# tie-flash-cfg.net
KiCad netlist of a schematic drawn in Altium Designer
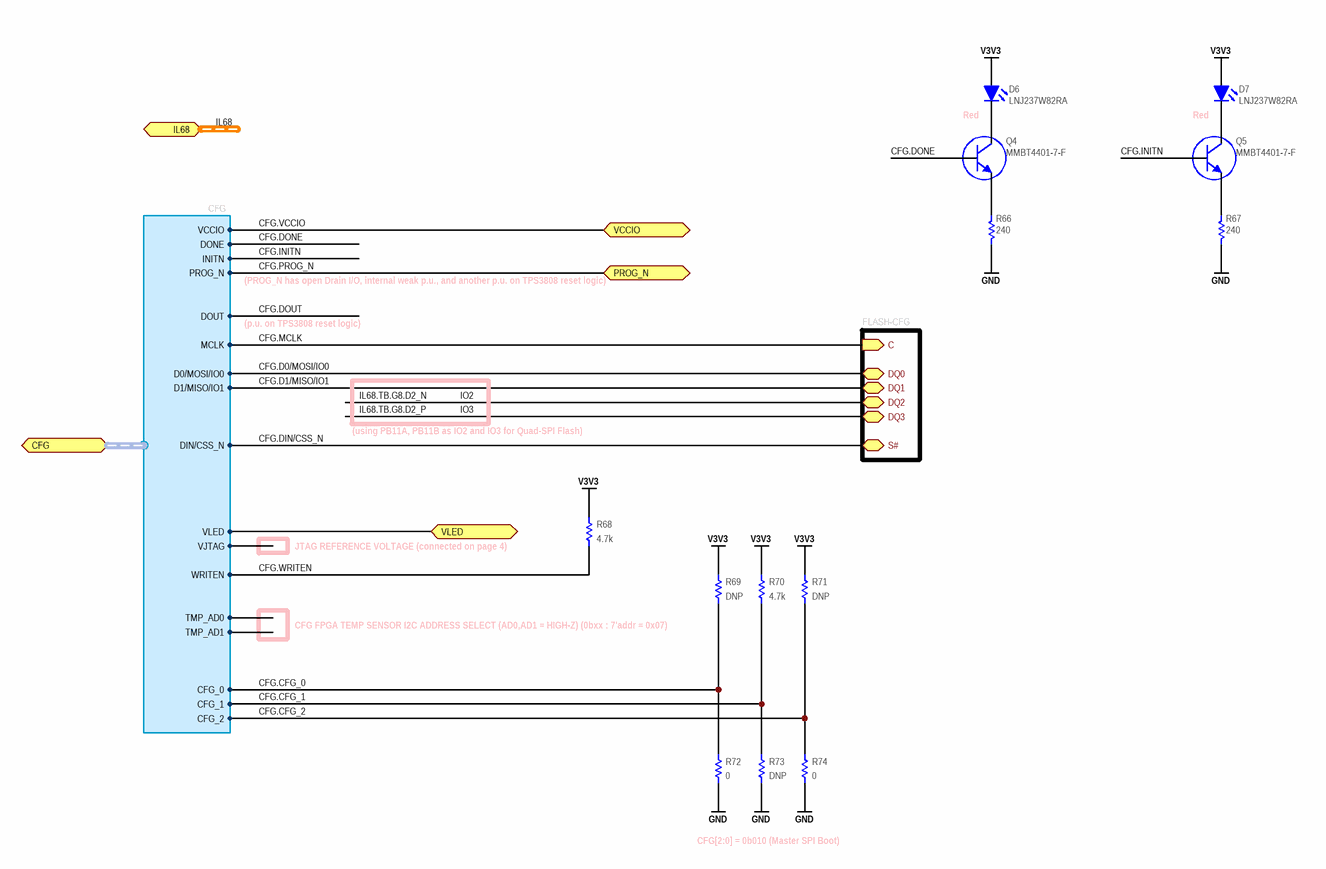
[diagram p0: tie-flash-cfg.SchDoc]

(export (version "E")
  (design (tool "Eeschema 10.0.6"))
  (components
    (comp (ref "D6")
      (value "LNJ237W82RA")
      (footprint "0603_LED")
      (description "LED, SMT 0603, Color Red, 5mA, 1.85V")
      (fields (field (name "MANUFACTURER") "Panasonic"))
      (libsource (lib "generic") (part "LED0603RD"))
    )
    (comp (ref "D7")
      (value "LNJ237W82RA")
      (footprint "0603_LED")
      (description "LED, SMT 0603, Color Red, 5mA, 1.85V")
      (fields (field (name "MANUFACTURER") "Panasonic"))
      (libsource (lib "generic") (part "LED0603RD"))
    )
    (comp (ref "Q4")
      (value "MMBT4401-7-F")
      (footprint "generic:SOT23")
      (description "NPN Small Signal Transistor SMD SOT-23")
      (fields (field (name "MANUFACTURER P/N") "MMBT4401-7-F") (field (name "MANUFACTURER") "Diodes, Inc."))
      (libsource (lib "diodes_inc") (part "MMBT4401-7-F"))
    )
    (comp (ref "Q5")
      (value "MMBT4401-7-F")
      (footprint "generic:SOT23")
      (description "NPN Small Signal Transistor SMD SOT-23")
      (fields (field (name "MANUFACTURER P/N") "MMBT4401-7-F") (field (name "MANUFACTURER") "Diodes, Inc."))
      (libsource (lib "diodes_inc") (part "MMBT4401-7-F"))
    )
    (comp (ref "R66")
      (value "240")
      (footprint "RESC1005X40N")
      (description "Thick Film Resistor 240 ±1% 0.1W 75V 0402")
      (fields (field (name "TOLERANCE") "±1%") (field (name "MANUFACTURER") "Panasonic"))
      (libsource (lib "generic") (part "RES"))
    )
    (comp (ref "R67")
      (value "240")
      (footprint "RESC1005X40N")
      (description "Thick Film Resistor 240 ±1% 0.1W 75V 0402")
      (fields (field (name "TOLERANCE") "±1%") (field (name "MANUFACTURER") "Panasonic"))
      (libsource (lib "generic") (part "RES"))
    )
    (comp (ref "R68")
      (value "4.7k")
      (footprint "RESC1005X40N")
      (description "Thick Film Resistor 4.7k ±1% 0.1W 75V 0402")
      (fields (field (name "TOLERANCE") "±1%") (field (name "MANUFACTURER") "Panasonic"))
      (libsource (lib "generic") (part "RES"))
    )
    (comp (ref "R69")
      (value "ERJ-3EKF4701V")
      (footprint "RESC1608X55N")
      (description "Thick Film Resistor 4.7k ±1% 0.1W 50V 0603")
      (fields
        (field (name "TOLERANCE") "±1%")
        (field (name "MANUFACTURER") "Panasonic")
        (field (name "DO NOT PLACE") "DNP")
      )
      (libsource (lib "generic") (part "RES"))
    )
    (comp (ref "R70")
      (value "4.7k")
      (footprint "RESC1608X55N")
      (description "Thick Film Resistor 4.7k ±1% 0.1W 50V 0603")
      (fields (field (name "TOLERANCE") "±1%") (field (name "MANUFACTURER") "Panasonic"))
      (libsource (lib "generic") (part "RES"))
    )
    (comp (ref "R71")
      (value "ERJ-3EKF4701V")
      (footprint "RESC1608X55N")
      (description "Thick Film Resistor 4.7k ±1% 0.1W 50V 0603")
      (fields
        (field (name "TOLERANCE") "±1%")
        (field (name "MANUFACTURER") "Panasonic")
        (field (name "DO NOT PLACE") "DNP")
      )
      (libsource (lib "generic") (part "RES"))
    )
    (comp (ref "R72")
      (value "0")
      (footprint "RESC1608X55N")
      (description "Thick Film Resistor Jumper 0 1A 0603")
      (fields (field (name "TOLERANCE") "±1%") (field (name "MANUFACTURER") "Panasonic"))
      (libsource (lib "generic") (part "RES"))
    )
    (comp (ref "R73")
      (value "ERJ-3GEY0R00V")
      (footprint "RESC1608X55N")
      (description "Thick Film Resistor Jumper 0 1A 0603")
      (fields
        (field (name "TOLERANCE") "±1%")
        (field (name "MANUFACTURER") "Panasonic")
        (field (name "DO NOT PLACE") "DNP")
      )
      (libsource (lib "generic") (part "RES"))
    )
    (comp (ref "R74")
      (value "0")
      (footprint "RESC1608X55N")
      (description "Thick Film Resistor Jumper 0 1A 0603")
      (fields (field (name "TOLERANCE") "±1%") (field (name "MANUFACTURER") "Panasonic"))
      (libsource (lib "generic") (part "RES"))
    )
  )
  (nets
    (net (code "3") (name "/CFG.CFG_0") (class "Default")
      (node (ref "R69") (pin "1") (pinfunction "1_1") (pintype "passive"))
      (node (ref "R72") (pin "2") (pinfunction "2_2") (pintype "passive"))
    )
    (net (code "4") (name "/CFG.CFG_1") (class "Default")
      (node (ref "R70") (pin "1") (pinfunction "1_1") (pintype "passive"))
      (node (ref "R73") (pin "2") (pinfunction "2_2") (pintype "passive"))
    )
    (net (code "5") (name "/CFG.CFG_2") (class "Default")
      (node (ref "R71") (pin "1") (pinfunction "1_1") (pintype "passive"))
      (node (ref "R74") (pin "2") (pinfunction "2_2") (pintype "passive"))
    )
    (net (code "9") (name "/CFG.DONE") (class "Default")
      (node (ref "Q4") (pin "1") (pinfunction "B_1") (pintype "passive"))
    )
    (net (code "11") (name "/CFG.INITN") (class "Default")
      (node (ref "Q5") (pin "1") (pinfunction "B_1") (pintype "passive"))
    )
    (net (code "15") (name "/CFG.WRITEN") (class "Default")
      (node (ref "R68") (pin "1") (pinfunction "1_1") (pintype "passive"))
    )
    (net (code "21") (name "GND") (class "Default")
      (node (ref "R66") (pin "2") (pinfunction "2_2") (pintype "passive"))
      (node (ref "R67") (pin "2") (pinfunction "2_2") (pintype "passive"))
      (node (ref "R72") (pin "1") (pinfunction "1_1") (pintype "passive"))
      (node (ref "R73") (pin "1") (pinfunction "1_1") (pintype "passive"))
      (node (ref "R74") (pin "1") (pinfunction "1_1") (pintype "passive"))
    )
    (net (code "22") (name "Net-(D6-K)") (class "Default")
      (node (ref "D6") (pin "2") (pinfunction "K_2") (pintype "passive"))
      (node (ref "Q4") (pin "3") (pinfunction "C_3") (pintype "passive"))
    )
    (net (code "23") (name "Net-(D7-K)") (class "Default")
      (node (ref "D7") (pin "2") (pinfunction "K_2") (pintype "passive"))
      (node (ref "Q5") (pin "3") (pinfunction "C_3") (pintype "passive"))
    )
    (net (code "24") (name "Net-(Q4-E)") (class "Default")
      (node (ref "Q4") (pin "2") (pinfunction "E_2") (pintype "passive"))
      (node (ref "R66") (pin "1") (pinfunction "1_1") (pintype "passive"))
    )
    (net (code "25") (name "Net-(Q5-E)") (class "Default")
      (node (ref "Q5") (pin "2") (pinfunction "E_2") (pintype "passive"))
      (node (ref "R67") (pin "1") (pinfunction "1_1") (pintype "passive"))
    )
    (net (code "26") (name "V3V3") (class "Default")
      (node (ref "D6") (pin "1") (pinfunction "A_1") (pintype "passive"))
      (node (ref "D7") (pin "1") (pinfunction "A_1") (pintype "passive"))
      (node (ref "R68") (pin "2") (pinfunction "2_2") (pintype "passive"))
      (node (ref "R69") (pin "2") (pinfunction "2_2") (pintype "passive"))
      (node (ref "R70") (pin "2") (pinfunction "2_2") (pintype "passive"))
      (node (ref "R71") (pin "2") (pinfunction "2_2") (pintype "passive"))
    )
  )
)
